# M3_Discrete_Interface.net
KiCad netlist of a schematic drawn in Altium Designer
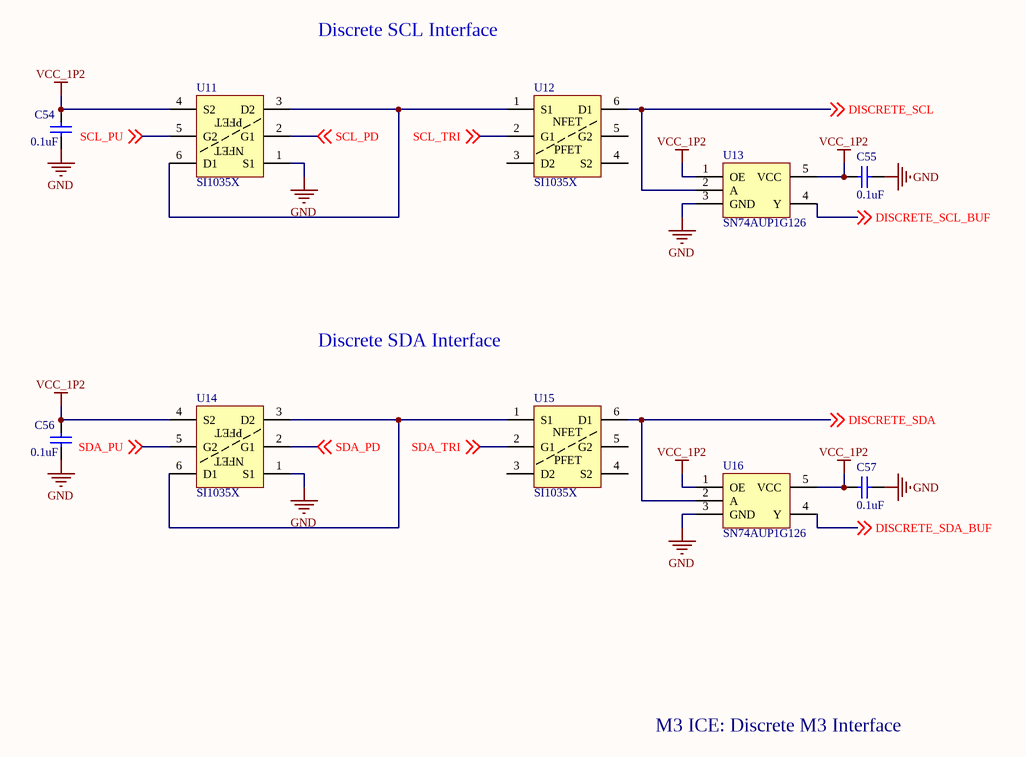
[diagram p0: M3_Discrete_Interface.SchDoc]

(export (version "E")
  (design (tool "Eeschema 10.0.6"))
  (components
    (comp (ref "C54")
      (value "0.1uF")
      (footprint "1608[0603]")
      (description "Capacitor (Semiconductor SIM Model)")
      (fields
        (field (name "DISTPARTNO") "445-1317-1-ND")
        (field (name "MANPARTNO") "C1608X7R1C104K")
        (field (name "PUBLISHER") "Altium Limited")
      )
      (libsource (lib "Miscellaneous Devices") (part "Cap Semi"))
    )
    (comp (ref "C55")
      (value "0.1uF")
      (footprint "1608[0603]")
      (description "Capacitor (Semiconductor SIM Model)")
      (fields
        (field (name "DISTPARTNO") "445-1317-1-ND")
        (field (name "MANPARTNO") "C1608X7R1C104K")
        (field (name "PUBLISHER") "Altium Limited")
      )
      (libsource (lib "Miscellaneous Devices") (part "Cap Semi"))
    )
    (comp (ref "C56")
      (value "0.1uF")
      (footprint "1608[0603]")
      (description "Capacitor (Semiconductor SIM Model)")
      (fields
        (field (name "DISTPARTNO") "445-1317-1-ND")
        (field (name "MANPARTNO") "C1608X7R1C104K")
        (field (name "PUBLISHER") "Altium Limited")
      )
      (libsource (lib "Miscellaneous Devices") (part "Cap Semi"))
    )
    (comp (ref "C57")
      (value "0.1uF")
      (footprint "1608[0603]")
      (description "Capacitor (Semiconductor SIM Model)")
      (fields
        (field (name "DISTPARTNO") "445-1317-1-ND")
        (field (name "MANPARTNO") "C1608X7R1C104K")
        (field (name "PUBLISHER") "Altium Limited")
      )
      (libsource (lib "Miscellaneous Devices") (part "Cap Semi"))
    )
    (comp (ref "U11")
      (value "SI1035X")
      (footprint "SC-89-6")
      (description "Complementary N- and P-Channel 20 V (D-S) MOSFET")
      (fields (field (name "DISTPARTNO") "SI1035X-T1-GE3CT-ND") (field (name "MANPARTNO") "SI1035X-T1-GE3"))
      (libsource (lib "") (part "SI1035X_1"))
    )
    (comp (ref "U12")
      (value "SI1035X")
      (footprint "SC-89-6")
      (description "Complementary N- and P-Channel 20 V (D-S) MOSFET")
      (fields (field (name "DISTPARTNO") "SI1035X-T1-GE3CT-ND") (field (name "MANPARTNO") "SI1035X-T1-GE3"))
      (libsource (lib "M3") (part "SI1035X"))
    )
    (comp (ref "U13")
      (value "SN74AUP1G126")
      (footprint "SOT-753")
      (description "LOW-POWER SINGLE BUS BUFFER GATE WITH 3-STATE OUTPUT")
      (fields (field (name "DISTPARTNO") "296-18005-1-ND") (field (name "MANPARTNO") "SN74AUP1G126DBVR"))
      (libsource (lib "M3") (part "SN74AUP1G126"))
    )
    (comp (ref "U14")
      (value "SI1035X")
      (footprint "SC-89-6")
      (description "Complementary N- and P-Channel 20 V (D-S) MOSFET")
      (fields (field (name "DISTPARTNO") "SI1035X-T1-GE3CT-ND") (field (name "MANPARTNO") "SI1035X-T1-GE3"))
      (libsource (lib "") (part "SI1035X_1"))
    )
    (comp (ref "U15")
      (value "SI1035X")
      (footprint "SC-89-6")
      (description "Complementary N- and P-Channel 20 V (D-S) MOSFET")
      (fields (field (name "DISTPARTNO") "SI1035X-T1-GE3CT-ND") (field (name "MANPARTNO") "SI1035X-T1-GE3"))
      (libsource (lib "M3") (part "SI1035X"))
    )
    (comp (ref "U16")
      (value "SN74AUP1G126")
      (footprint "SOT-753")
      (description "LOW-POWER SINGLE BUS BUFFER GATE WITH 3-STATE OUTPUT")
      (fields (field (name "DISTPARTNO") "296-18005-1-ND") (field (name "MANPARTNO") "SN74AUP1G126DBVR"))
      (libsource (lib "M3") (part "SN74AUP1G126"))
    )
  )
  (nets
    (net (code "1") (name "DISCRETE_SCL") (class "Default")
      (node (ref "U12") (pin "6") (pinfunction "D1_6") (pintype "passive"))
      (node (ref "U13") (pin "2") (pinfunction "A_2") (pintype "passive"))
    )
    (net (code "2") (name "DISCRETE_SCL_BUF") (class "Default")
      (node (ref "U13") (pin "4") (pinfunction "Y_4") (pintype "passive"))
    )
    (net (code "3") (name "DISCRETE_SDA") (class "Default")
      (node (ref "U15") (pin "6") (pinfunction "D1_6") (pintype "passive"))
      (node (ref "U16") (pin "2") (pinfunction "A_2") (pintype "passive"))
    )
    (net (code "4") (name "DISCRETE_SDA_BUF") (class "Default")
      (node (ref "U16") (pin "4") (pinfunction "Y_4") (pintype "passive"))
    )
    (net (code "5") (name "GND") (class "Default")
      (node (ref "C54") (pin "1") (pinfunction "1_1") (pintype "passive"))
      (node (ref "C55") (pin "1") (pinfunction "1_1") (pintype "passive"))
      (node (ref "C56") (pin "1") (pinfunction "1_1") (pintype "passive"))
      (node (ref "C57") (pin "1") (pinfunction "1_1") (pintype "passive"))
      (node (ref "U11") (pin "1") (pinfunction "S1_1") (pintype "passive"))
      (node (ref "U13") (pin "3") (pinfunction "GND_3") (pintype "passive"))
      (node (ref "U14") (pin "1") (pinfunction "S1_1") (pintype "passive"))
      (node (ref "U16") (pin "3") (pinfunction "GND_3") (pintype "passive"))
    )
    (net (code "6") (name "Net-(U11-D1)") (class "Default")
      (node (ref "U11") (pin "3") (pinfunction "D2_3") (pintype "passive"))
      (node (ref "U11") (pin "6") (pinfunction "D1_6") (pintype "passive"))
      (node (ref "U12") (pin "1") (pinfunction "S1_1") (pintype "passive"))
    )
    (net (code "7") (name "Net-(U14-D1)") (class "Default")
      (node (ref "U14") (pin "3") (pinfunction "D2_3") (pintype "passive"))
      (node (ref "U14") (pin "6") (pinfunction "D1_6") (pintype "passive"))
      (node (ref "U15") (pin "1") (pinfunction "S1_1") (pintype "passive"))
    )
    (net (code "8") (name "SCL_PD") (class "Default")
      (node (ref "U11") (pin "2") (pinfunction "G1_2") (pintype "passive"))
    )
    (net (code "9") (name "SCL_PU") (class "Default")
      (node (ref "U11") (pin "5") (pinfunction "G2_5") (pintype "passive"))
    )
    (net (code "10") (name "SCL_TRI") (class "Default")
      (node (ref "U12") (pin "2") (pinfunction "G1_2") (pintype "passive"))
    )
    (net (code "11") (name "SDA_PD") (class "Default")
      (node (ref "U14") (pin "2") (pinfunction "G1_2") (pintype "passive"))
    )
    (net (code "12") (name "SDA_PU") (class "Default")
      (node (ref "U14") (pin "5") (pinfunction "G2_5") (pintype "passive"))
    )
    (net (code "13") (name "SDA_TRI") (class "Default")
      (node (ref "U15") (pin "2") (pinfunction "G1_2") (pintype "passive"))
    )
    (net (code "14") (name "VCC_1P2") (class "Default")
      (node (ref "C54") (pin "2") (pinfunction "2_2") (pintype "passive"))
      (node (ref "C55") (pin "2") (pinfunction "2_2") (pintype "passive"))
      (node (ref "C56") (pin "2") (pinfunction "2_2") (pintype "passive"))
      (node (ref "C57") (pin "2") (pinfunction "2_2") (pintype "passive"))
      (node (ref "U11") (pin "4") (pinfunction "S2_4") (pintype "passive"))
      (node (ref "U13") (pin "1") (pinfunction "OE_1") (pintype "passive"))
      (node (ref "U13") (pin "5") (pinfunction "VCC_5") (pintype "passive"))
      (node (ref "U14") (pin "4") (pinfunction "S2_4") (pintype "passive"))
      (node (ref "U16") (pin "1") (pinfunction "OE_1") (pintype "passive"))
      (node (ref "U16") (pin "5") (pinfunction "VCC_5") (pintype "passive"))
    )
    (net (code "15") (name "unconnected-(U12-D2-Pad3)") (class "Default")
      (node (ref "U12") (pin "3") (pinfunction "D2_3") (pintype "passive"))
    )
    (net (code "16") (name "unconnected-(U12-G2-Pad5)") (class "Default")
      (node (ref "U12") (pin "5") (pinfunction "G2_5") (pintype "passive"))
    )
    (net (code "17") (name "unconnected-(U12-S2-Pad4)") (class "Default")
      (node (ref "U12") (pin "4") (pinfunction "S2_4") (pintype "passive"))
    )
    (net (code "18") (name "unconnected-(U15-D2-Pad3)") (class "Default")
      (node (ref "U15") (pin "3") (pinfunction "D2_3") (pintype "passive"))
    )
    (net (code "19") (name "unconnected-(U15-G2-Pad5)") (class "Default")
      (node (ref "U15") (pin "5") (pinfunction "G2_5") (pintype "passive"))
    )
    (net (code "20") (name "unconnected-(U15-S2-Pad4)") (class "Default")
      (node (ref "U15") (pin "4") (pinfunction "S2_4") (pintype "passive"))
    )
  )
)
